# A702B.net
KiCad netlist of a schematic drawn in EAGLE
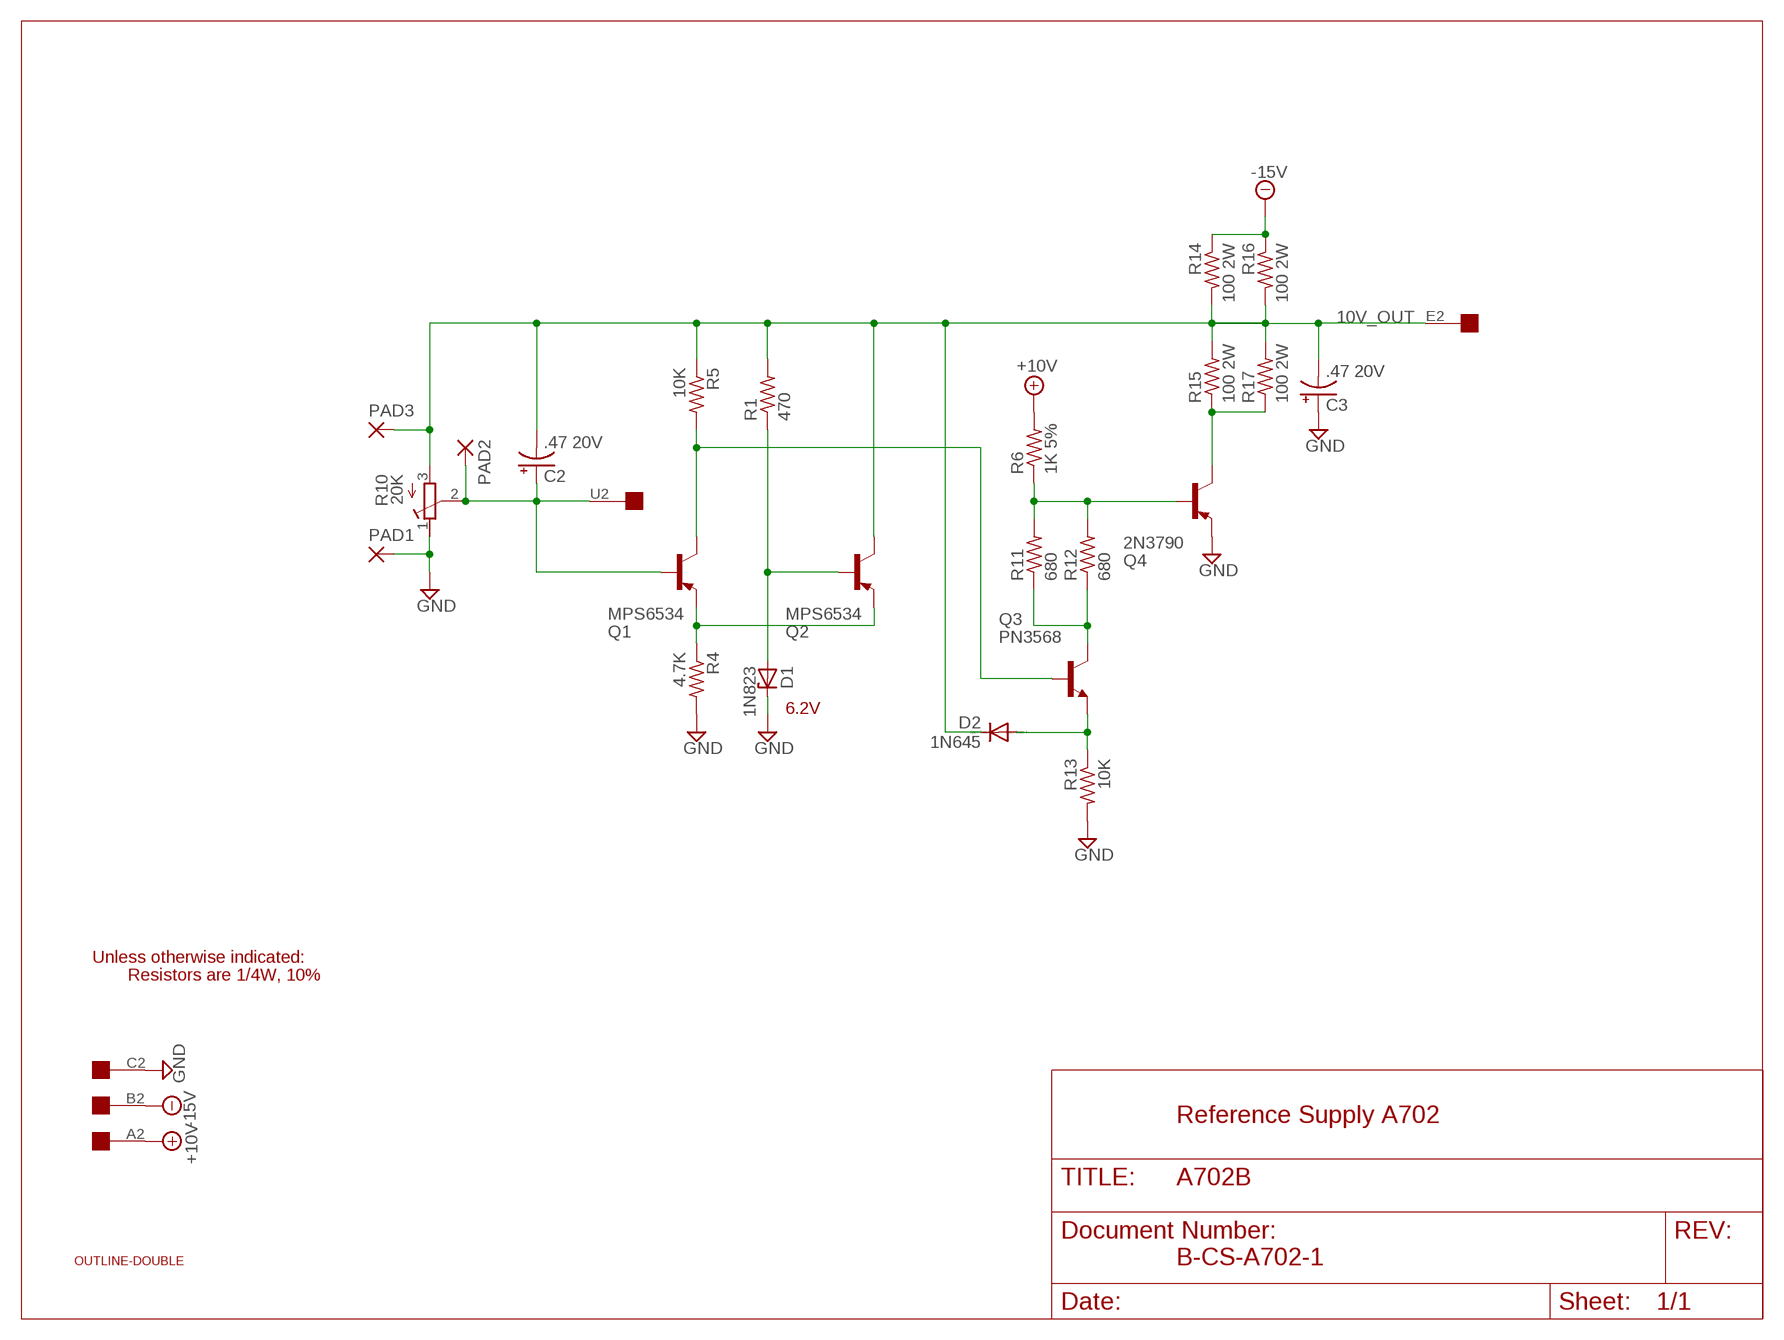
[diagram p0: schematic, sheet 1]

(export (version "E")
  (design (tool "Eeschema 10.0.6"))
  (components
    (comp (ref "C2")
      (value ".47 20V")
      (footprint "eagle-import:E22-6")
      (libsource (lib "eagle-import") (part "CPOL-USE22-6AXIAL"))
    )
    (comp (ref "C3")
      (value ".47 20V")
      (footprint "eagle-import:E22-6")
      (libsource (lib "eagle-import") (part "CPOL-USE22-6AXIAL"))
    )
    (comp (ref "D1")
      (value "1N823")
      (footprint "eagle-import:DO35Z10")
      (libsource (lib "eagle-import") (part "1N821"))
    )
    (comp (ref "D2")
      (value "1N645")
      (footprint "eagle-import:DO35-10")
      (libsource (lib "eagle-import") (part "1N4148DO35-10"))
    )
    (comp (ref "PAD1")
      (value "2,54/0,8")
      (footprint "eagle-import:2,54_0,8")
      (libsource (lib "eagle-import") (part "2,54/0,8"))
    )
    (comp (ref "PAD2")
      (value "2,54/0,8")
      (footprint "eagle-import:2,54_0,8")
      (libsource (lib "eagle-import") (part "2,54/0,8"))
    )
    (comp (ref "PAD3")
      (value "2,54/0,8")
      (footprint "eagle-import:2,54_0,8")
      (libsource (lib "eagle-import") (part "2,54/0,8"))
    )
    (comp (ref "Q1")
      (value "MPS6534")
      (footprint "eagle-import:TO39")
      (libsource (lib "eagle-import") (part "2N2904A"))
    )
    (comp (ref "Q2")
      (value "MPS6534")
      (footprint "eagle-import:TO39")
      (libsource (lib "eagle-import") (part "2N2904A"))
    )
    (comp (ref "Q3")
      (value "PN3568")
      (footprint "eagle-import:TO5")
      (libsource (lib "eagle-import") (part "2N2219"))
    )
    (comp (ref "Q4")
      (value "2N3790")
      (footprint "eagle-import:TO3")
      (libsource (lib "eagle-import") (part "-PNP-TO3"))
    )
    (comp (ref "R1")
      (value "470")
      (footprint "eagle-import:0207_10")
      (libsource (lib "eagle-import") (part "R-US_0207/10"))
    )
    (comp (ref "R4")
      (value "4.7K")
      (footprint "eagle-import:0207_10")
      (libsource (lib "eagle-import") (part "R-US_0207/10"))
    )
    (comp (ref "R5")
      (value "10K")
      (footprint "eagle-import:0207_10")
      (libsource (lib "eagle-import") (part "R-US_0207/10"))
    )
    (comp (ref "R6")
      (value "1K 5%")
      (footprint "eagle-import:0207_10")
      (libsource (lib "eagle-import") (part "R-US_0207/10"))
    )
    (comp (ref "R10")
      (value "20K")
      (footprint "eagle-import:3006Y")
      (libsource (lib "eagle-import") (part "275P"))
    )
    (comp (ref "R11")
      (value "680")
      (footprint "eagle-import:0207_10")
      (libsource (lib "eagle-import") (part "R-US_0207/10"))
    )
    (comp (ref "R12")
      (value "680")
      (footprint "eagle-import:0207_10")
      (libsource (lib "eagle-import") (part "R-US_0207/10"))
    )
    (comp (ref "R13")
      (value "10K")
      (footprint "eagle-import:0207_10")
      (libsource (lib "eagle-import") (part "R-US_0207/10"))
    )
    (comp (ref "R14")
      (value "100 2W")
      (footprint "eagle-import:P0817_22")
      (libsource (lib "eagle-import") (part "R-US_0817/22"))
    )
    (comp (ref "R15")
      (value "100 2W")
      (footprint "eagle-import:P0817_22")
      (libsource (lib "eagle-import") (part "R-US_0817/22"))
    )
    (comp (ref "R16")
      (value "100 2W")
      (footprint "eagle-import:P0817_22")
      (libsource (lib "eagle-import") (part "R-US_0817/22"))
    )
    (comp (ref "R17")
      (value "100 2W")
      (footprint "eagle-import:P0817_22")
      (libsource (lib "eagle-import") (part "R-US_0817/22"))
    )
    (comp (ref "U$1")
      (value "OUTLINE-DOUBLE")
      (footprint "eagle-import:DOUBLE")
      (libsource (lib "eagle-import") (part "OUTLINE-DOUBLE"))
    )
    (comp (ref "U$3")
      (value "EDGE-1")
      (footprint "eagle-import:EDGE-CON1")
      (libsource (lib "eagle-import") (part "EDGE-1"))
    )
  )
  (nets
    (net (code "1") (name "+10V") (class "Default")
      (node (ref "R6") (pin "2") (pinfunction "2_2") (pintype "passive"))
      (node (ref "U$3") (pin "A2") (pinfunction "1_A2") (pintype "bidirectional"))
    )
    (net (code "2") (name "-15V") (class "Default")
      (node (ref "R14") (pin "1") (pinfunction "1_1") (pintype "passive"))
      (node (ref "R16") (pin "1") (pinfunction "1_1") (pintype "passive"))
      (node (ref "U$3") (pin "B2") (pinfunction "1_B2") (pintype "bidirectional"))
    )
    (net (code "3") (name "/10V_OUT") (class "Default")
      (node (ref "C2") (pin "-") (pinfunction "-_-") (pintype "passive"))
      (node (ref "C3") (pin "-") (pinfunction "-_-") (pintype "passive"))
      (node (ref "D2") (pin "C") (pinfunction "C_C") (pintype "passive"))
      (node (ref "PAD3") (pin "1") (pinfunction "P_1") (pintype "passive"))
      (node (ref "Q2") (pin "3") (pinfunction "C_3") (pintype "passive"))
      (node (ref "R1") (pin "2") (pinfunction "2_2") (pintype "passive"))
      (node (ref "R10") (pin "3") (pinfunction "E_3") (pintype "passive"))
      (node (ref "R14") (pin "2") (pinfunction "2_2") (pintype "passive"))
      (node (ref "R15") (pin "2") (pinfunction "2_2") (pintype "passive"))
      (node (ref "R16") (pin "2") (pinfunction "2_2") (pintype "passive"))
      (node (ref "R17") (pin "2") (pinfunction "2_2") (pintype "passive"))
      (node (ref "R5") (pin "1") (pinfunction "1_1") (pintype "passive"))
      (node (ref "U$3") (pin "E2") (pinfunction "1_E2") (pintype "bidirectional"))
    )
    (net (code "4") (name "GND") (class "Default")
      (node (ref "C3") (pin "+") (pinfunction "+_+") (pintype "passive"))
      (node (ref "D1") (pin "C") (pinfunction "C_C") (pintype "passive"))
      (node (ref "PAD1") (pin "1") (pinfunction "P_1") (pintype "passive"))
      (node (ref "Q4") (pin "E") (pinfunction "E_E") (pintype "passive"))
      (node (ref "R10") (pin "1") (pinfunction "A_1") (pintype "passive"))
      (node (ref "R13") (pin "2") (pinfunction "2_2") (pintype "passive"))
      (node (ref "R4") (pin "2") (pinfunction "2_2") (pintype "passive"))
      (node (ref "U$3") (pin "C2") (pinfunction "1_C2") (pintype "bidirectional"))
    )
    (net (code "5") (name "Net-(PAD2-P)") (class "Default")
      (node (ref "C2") (pin "+") (pinfunction "+_+") (pintype "passive"))
      (node (ref "PAD2") (pin "1") (pinfunction "P_1") (pintype "passive"))
      (node (ref "Q1") (pin "2") (pinfunction "B_2") (pintype "passive"))
      (node (ref "R10") (pin "2") (pinfunction "S_2") (pintype "passive"))
      (node (ref "U$3") (pin "U2") (pinfunction "1_U2") (pintype "bidirectional"))
    )
    (net (code "6") (name "Net-(Q1-C)") (class "Default")
      (node (ref "Q1") (pin "3") (pinfunction "C_3") (pintype "passive"))
      (node (ref "Q3") (pin "2") (pinfunction "B_2") (pintype "passive"))
      (node (ref "R5") (pin "2") (pinfunction "2_2") (pintype "passive"))
    )
    (net (code "7") (name "Net-(Q1-E)") (class "Default")
      (node (ref "Q1") (pin "1") (pinfunction "E_1") (pintype "passive"))
      (node (ref "Q2") (pin "1") (pinfunction "E_1") (pintype "passive"))
      (node (ref "R4") (pin "1") (pinfunction "1_1") (pintype "passive"))
    )
    (net (code "8") (name "Net-(Q2-B)") (class "Default")
      (node (ref "D1") (pin "A") (pinfunction "A_A") (pintype "passive"))
      (node (ref "Q2") (pin "2") (pinfunction "B_2") (pintype "passive"))
      (node (ref "R1") (pin "1") (pinfunction "1_1") (pintype "passive"))
    )
    (net (code "9") (name "Net-(Q3-C)") (class "Default")
      (node (ref "Q3") (pin "3") (pinfunction "C_3") (pintype "passive"))
      (node (ref "R11") (pin "1") (pinfunction "1_1") (pintype "passive"))
      (node (ref "R12") (pin "1") (pinfunction "1_1") (pintype "passive"))
    )
    (net (code "10") (name "Net-(Q3-E)") (class "Default")
      (node (ref "D2") (pin "A") (pinfunction "A_A") (pintype "passive"))
      (node (ref "Q3") (pin "1") (pinfunction "E_1") (pintype "passive"))
      (node (ref "R13") (pin "1") (pinfunction "1_1") (pintype "passive"))
    )
    (net (code "11") (name "Net-(Q4-PadB)") (class "Default")
      (node (ref "Q4") (pin "B") (pinfunction "B_B") (pintype "passive"))
      (node (ref "R11") (pin "2") (pinfunction "2_2") (pintype "passive"))
      (node (ref "R12") (pin "2") (pinfunction "2_2") (pintype "passive"))
      (node (ref "R6") (pin "1") (pinfunction "1_1") (pintype "passive"))
    )
    (net (code "12") (name "Net-(Q4-PadC)") (class "Default")
      (node (ref "Q4") (pin "C") (pinfunction "C_C") (pintype "passive"))
      (node (ref "R15") (pin "1") (pinfunction "1_1") (pintype "passive"))
      (node (ref "R17") (pin "1") (pinfunction "1_1") (pintype "passive"))
    )
  )
)
